# led.net
KiCad netlist of a schematic drawn in Altium Designer
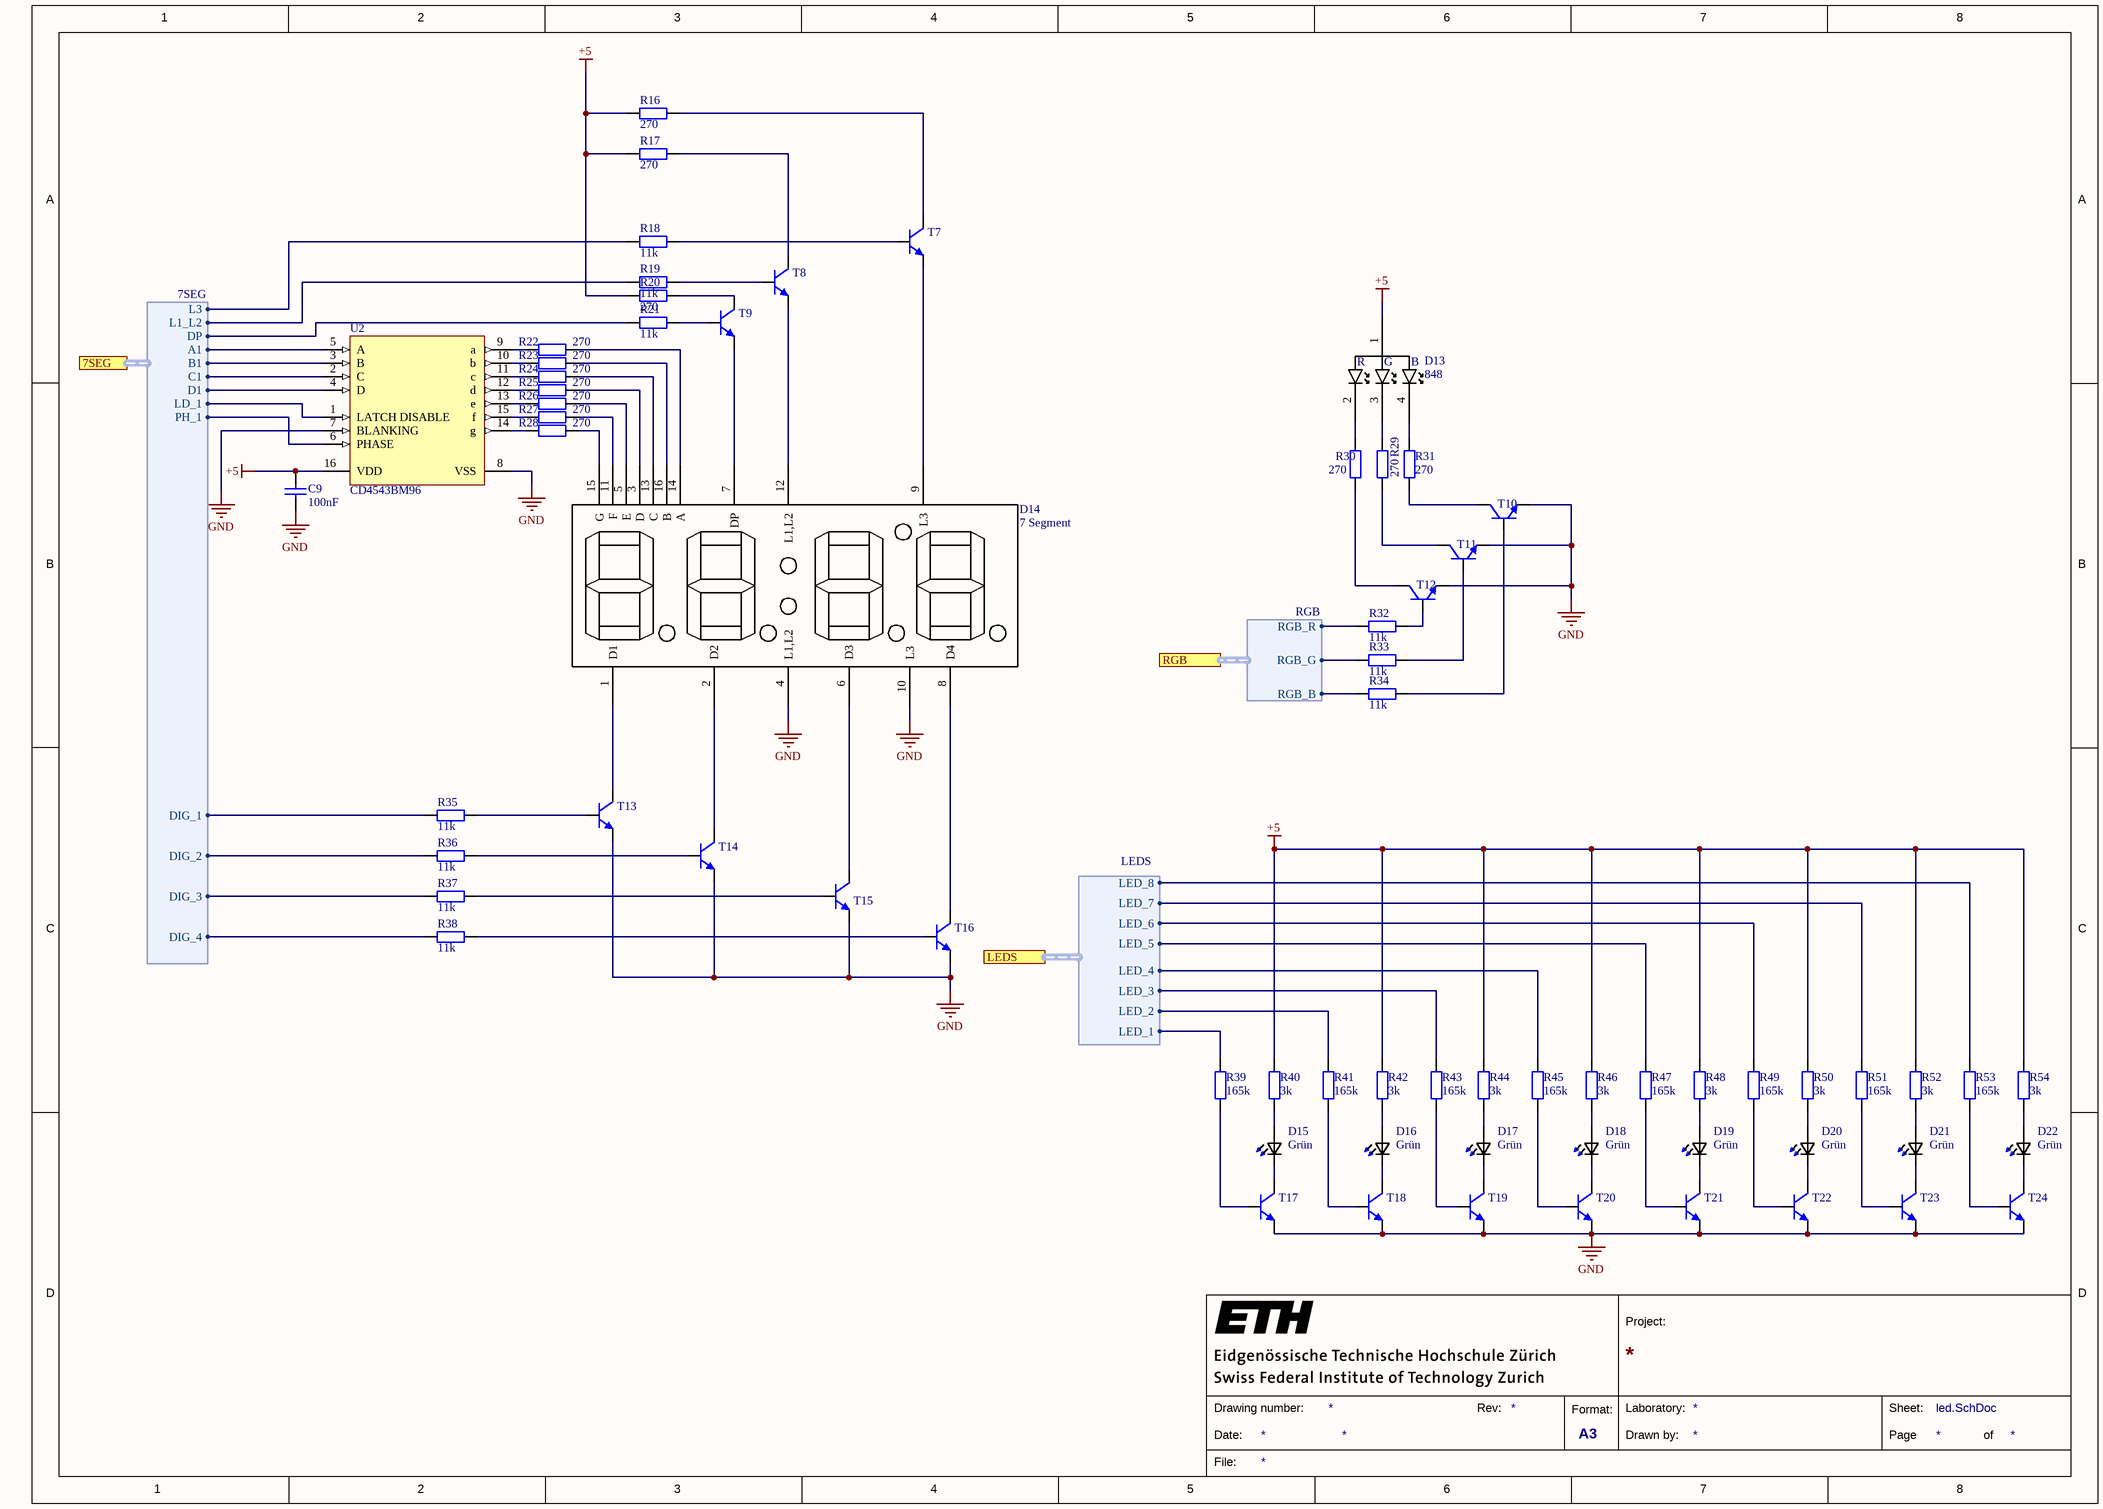
[diagram p0: led.SchDoc]

(export (version "E")
  (design (tool "Eeschema 10.0.6"))
  (components
    (comp (ref "C9")
      (value "100nF")
      (footprint "CAP_0603i_1608m -N")
      (description "capacitor")
      (libsource (lib "IDSC std generic parts") (part "Cap"))
    )
    (comp (ref "D13") (value "848") (footprint "Adafruit-848") (libsource (lib "LIB") (part "Adafruit-848")))
    (comp (ref "D14") (value "7 Segment") (footprint "TDCG1060M") (libsource (lib "LIB") (part "TDCG1060M")))
    (comp (ref "D15")
      (value "Grün")
      (footprint "*0603")
      (description "LED; SMD; 0603; gr黱; 35mcd; 1.6x0.8x0.55mm; 130掳; 2梅2.V; 20mA")
      (fields (field (name "MP") "LTST-C191KGKT") (field (name "DIGI-KEY_PART_NUMBER") "160-1446-1-ND"))
      (libsource (lib "Funk") (part "LTST-C191KGKT"))
    )
    (comp (ref "D16")
      (value "Grün")
      (footprint "*0603")
      (description "LED; SMD; 0603; gr黱; 35mcd; 1.6x0.8x0.55mm; 130掳; 2梅2.V; 20mA")
      (fields (field (name "MP") "LTST-C191KGKT") (field (name "DIGI-KEY_PART_NUMBER") "160-1446-1-ND"))
      (libsource (lib "Funk") (part "LTST-C191KGKT"))
    )
    (comp (ref "D17")
      (value "Grün")
      (footprint "*0603")
      (description "LED; SMD; 0603; gr黱; 35mcd; 1.6x0.8x0.55mm; 130掳; 2梅2.V; 20mA")
      (fields (field (name "MP") "LTST-C191KGKT") (field (name "DIGI-KEY_PART_NUMBER") "160-1446-1-ND"))
      (libsource (lib "Funk") (part "LTST-C191KGKT"))
    )
    (comp (ref "D18")
      (value "Grün")
      (footprint "*0603")
      (description "LED; SMD; 0603; gr黱; 35mcd; 1.6x0.8x0.55mm; 130掳; 2梅2.V; 20mA")
      (fields (field (name "MP") "LTST-C191KGKT") (field (name "DIGI-KEY_PART_NUMBER") "160-1446-1-ND"))
      (libsource (lib "Funk") (part "LTST-C191KGKT"))
    )
    (comp (ref "D19")
      (value "Grün")
      (footprint "*0603")
      (description "LED; SMD; 0603; gr黱; 35mcd; 1.6x0.8x0.55mm; 130掳; 2梅2.V; 20mA")
      (fields (field (name "MP") "LTST-C191KGKT") (field (name "DIGI-KEY_PART_NUMBER") "160-1446-1-ND"))
      (libsource (lib "Funk") (part "LTST-C191KGKT"))
    )
    (comp (ref "D20")
      (value "Grün")
      (footprint "*0603")
      (description "LED; SMD; 0603; gr黱; 35mcd; 1.6x0.8x0.55mm; 130掳; 2梅2.V; 20mA")
      (fields (field (name "MP") "LTST-C191KGKT") (field (name "DIGI-KEY_PART_NUMBER") "160-1446-1-ND"))
      (libsource (lib "Funk") (part "LTST-C191KGKT"))
    )
    (comp (ref "D21")
      (value "Grün")
      (footprint "*0603")
      (description "LED; SMD; 0603; gr黱; 35mcd; 1.6x0.8x0.55mm; 130掳; 2梅2.V; 20mA")
      (fields (field (name "MP") "LTST-C191KGKT") (field (name "DIGI-KEY_PART_NUMBER") "160-1446-1-ND"))
      (libsource (lib "Funk") (part "LTST-C191KGKT"))
    )
    (comp (ref "D22")
      (value "Grün")
      (footprint "*0603")
      (description "LED; SMD; 0603; gr黱; 35mcd; 1.6x0.8x0.55mm; 130掳; 2梅2.V; 20mA")
      (fields (field (name "MP") "LTST-C191KGKT") (field (name "DIGI-KEY_PART_NUMBER") "160-1446-1-ND"))
      (libsource (lib "Funk") (part "LTST-C191KGKT"))
    )
    (comp (ref "R16")
      (value "270")
      (footprint "RES_0603i_1608m -N")
      (description "Resistor")
      (libsource (lib "IDSC std generic parts") (part "Res"))
    )
    (comp (ref "R17")
      (value "270")
      (footprint "RES_0603i_1608m -N")
      (description "Resistor")
      (libsource (lib "IDSC std generic parts") (part "Res"))
    )
    (comp (ref "R18")
      (value "11k")
      (footprint "RES_0603i_1608m -N")
      (description "Resistor")
      (libsource (lib "IDSC std generic parts") (part "Res"))
    )
    (comp (ref "R19")
      (value "11k")
      (footprint "RES_0603i_1608m -N")
      (description "Resistor")
      (libsource (lib "IDSC std generic parts") (part "Res"))
    )
    (comp (ref "R20")
      (value "270")
      (footprint "RES_0603i_1608m -N")
      (description "Resistor")
      (libsource (lib "") (part "Res_2"))
    )
    (comp (ref "R21")
      (value "11k")
      (footprint "RES_0603i_1608m -N")
      (description "Resistor")
      (libsource (lib "") (part "Res_2"))
    )
    (comp (ref "R22")
      (value "270")
      (footprint "RES_0603i_1608m -N")
      (description "Resistor")
      (libsource (lib "IDSC std generic parts") (part "Res"))
    )
    (comp (ref "R23")
      (value "270")
      (footprint "RES_0603i_1608m -N")
      (description "Resistor")
      (libsource (lib "IDSC std generic parts") (part "Res"))
    )
    (comp (ref "R24")
      (value "270")
      (footprint "RES_0603i_1608m -N")
      (description "Resistor")
      (libsource (lib "IDSC std generic parts") (part "Res"))
    )
    (comp (ref "R25")
      (value "270")
      (footprint "RES_0603i_1608m -N")
      (description "Resistor")
      (libsource (lib "IDSC std generic parts") (part "Res"))
    )
    (comp (ref "R26")
      (value "270")
      (footprint "RES_0603i_1608m -N")
      (description "Resistor")
      (libsource (lib "IDSC std generic parts") (part "Res"))
    )
    (comp (ref "R27")
      (value "270")
      (footprint "RES_0603i_1608m -N")
      (description "Resistor")
      (libsource (lib "IDSC std generic parts") (part "Res"))
    )
    (comp (ref "R28")
      (value "270")
      (footprint "RES_0603i_1608m -N")
      (description "Resistor")
      (libsource (lib "IDSC std generic parts") (part "Res"))
    )
    (comp (ref "R29")
      (value "270")
      (footprint "RES_0603i_1608m -N")
      (description "Resistor")
      (libsource (lib "") (part "Res_1"))
    )
    (comp (ref "R30")
      (value "270")
      (footprint "RES_0603i_1608m -N")
      (description "Resistor")
      (libsource (lib "") (part "Res_1"))
    )
    (comp (ref "R31")
      (value "270")
      (footprint "RES_0603i_1608m -N")
      (description "Resistor")
      (libsource (lib "") (part "Res_1"))
    )
    (comp (ref "R32")
      (value "11k")
      (footprint "RES_0603i_1608m -N")
      (description "Resistor")
      (libsource (lib "") (part "Res_2"))
    )
    (comp (ref "R33")
      (value "11k")
      (footprint "RES_0603i_1608m -N")
      (description "Resistor")
      (libsource (lib "") (part "Res_2"))
    )
    (comp (ref "R34")
      (value "11k")
      (footprint "RES_0603i_1608m -N")
      (description "Resistor")
      (libsource (lib "") (part "Res_2"))
    )
    (comp (ref "R35")
      (value "11k")
      (footprint "RES_0603i_1608m -N")
      (description "Resistor")
      (libsource (lib "") (part "Res_2"))
    )
    (comp (ref "R36")
      (value "11k")
      (footprint "RES_0603i_1608m -N")
      (description "Resistor")
      (libsource (lib "") (part "Res_2"))
    )
    (comp (ref "R37")
      (value "11k")
      (footprint "RES_0603i_1608m -N")
      (description "Resistor")
      (libsource (lib "") (part "Res_2"))
    )
    (comp (ref "R38")
      (value "11k")
      (footprint "RES_0603i_1608m -N")
      (description "Resistor")
      (libsource (lib "") (part "Res_2"))
    )
    (comp (ref "R39")
      (value "165k")
      (footprint "RES_0603i_1608m -N")
      (description "Resistor")
      (libsource (lib "") (part "Res_1"))
    )
    (comp (ref "R40")
      (value "3k")
      (footprint "RES_0603i_1608m -N")
      (description "Resistor")
      (libsource (lib "") (part "Res_1"))
    )
    (comp (ref "R41")
      (value "165k")
      (footprint "RES_0603i_1608m -N")
      (description "Resistor")
      (libsource (lib "") (part "Res_1"))
    )
    (comp (ref "R42")
      (value "3k")
      (footprint "RES_0603i_1608m -N")
      (description "Resistor")
      (libsource (lib "") (part "Res_1"))
    )
    (comp (ref "R43")
      (value "165k")
      (footprint "RES_0603i_1608m -N")
      (description "Resistor")
      (libsource (lib "") (part "Res_1"))
    )
    (comp (ref "R44")
      (value "3k")
      (footprint "RES_0603i_1608m -N")
      (description "Resistor")
      (libsource (lib "") (part "Res_1"))
    )
    (comp (ref "R45")
      (value "165k")
      (footprint "RES_0603i_1608m -N")
      (description "Resistor")
      (libsource (lib "") (part "Res_1"))
    )
    (comp (ref "R46")
      (value "3k")
      (footprint "RES_0603i_1608m -N")
      (description "Resistor")
      (libsource (lib "") (part "Res_1"))
    )
    (comp (ref "R47")
      (value "165k")
      (footprint "RES_0603i_1608m -N")
      (description "Resistor")
      (libsource (lib "") (part "Res_1"))
    )
    (comp (ref "R48")
      (value "3k")
      (footprint "RES_0603i_1608m -N")
      (description "Resistor")
      (libsource (lib "") (part "Res_1"))
    )
    (comp (ref "R49")
      (value "165k")
      (footprint "RES_0603i_1608m -N")
      (description "Resistor")
      (libsource (lib "") (part "Res_1"))
    )
    (comp (ref "R50")
      (value "3k")
      (footprint "RES_0603i_1608m -N")
      (description "Resistor")
      (libsource (lib "") (part "Res_1"))
    )
    (comp (ref "R51")
      (value "165k")
      (footprint "RES_0603i_1608m -N")
      (description "Resistor")
      (libsource (lib "") (part "Res_1"))
    )
    (comp (ref "R52")
      (value "3k")
      (footprint "RES_0603i_1608m -N")
      (description "Resistor")
      (libsource (lib "") (part "Res_1"))
    )
    (comp (ref "R53")
      (value "165k")
      (footprint "RES_0603i_1608m -N")
      (description "Resistor")
      (libsource (lib "") (part "Res_1"))
    )
    (comp (ref "R54")
      (value "3k")
      (footprint "RES_0603i_1608m -N")
      (description "Resistor")
      (libsource (lib "") (part "Res_1"))
    )
    (comp (ref "T7")
      (value "Part Number: MMBT3904-7-F")
      (footprint "SOT-23-M")
      (description "No Description Available")
      (fields
        (field (name "MANUFACTURER_PART_NUMBER") "MMBT3904-7-F")
        (field (name "COPYRIGHT") "Copyright (C) 2018 Accelerated Designs. All rights reserved")
      )
      (libsource (lib "Funk") (part "MMBT3904-7-F"))
    )
    (comp (ref "T8")
      (value "Part Number: MMBT3904-7-F")
      (footprint "SOT-23-M")
      (description "No Description Available")
      (fields
        (field (name "MANUFACTURER_PART_NUMBER") "MMBT3904-7-F")
        (field (name "COPYRIGHT") "Copyright (C) 2018 Accelerated Designs. All rights reserved")
      )
      (libsource (lib "Funk") (part "MMBT3904-7-F"))
    )
    (comp (ref "T9")
      (value "Part Number: MMBT3904-7-F")
      (footprint "SOT-23-M")
      (description "No Description Available")
      (fields
        (field (name "MANUFACTURER_PART_NUMBER") "MMBT3904-7-F")
        (field (name "COPYRIGHT") "Copyright (C) 2018 Accelerated Designs. All rights reserved")
      )
      (libsource (lib "Funk") (part "MMBT3904-7-F"))
    )
    (comp (ref "T10")
      (value "Part Number: MMBT3904-7-F")
      (footprint "SOT-23-M")
      (description "No Description Available")
      (fields
        (field (name "MANUFACTURER_PART_NUMBER") "MMBT3904-7-F")
        (field (name "COPYRIGHT") "Copyright (C) 2018 Accelerated Designs. All rights reserved")
      )
      (libsource (lib "Funk") (part "MMBT3904-7-F"))
    )
    (comp (ref "T11")
      (value "Part Number: MMBT3904-7-F")
      (footprint "SOT-23-M")
      (description "No Description Available")
      (fields
        (field (name "MANUFACTURER_PART_NUMBER") "MMBT3904-7-F")
        (field (name "COPYRIGHT") "Copyright (C) 2018 Accelerated Designs. All rights reserved")
      )
      (libsource (lib "Funk") (part "MMBT3904-7-F"))
    )
    (comp (ref "T12")
      (value "Part Number: MMBT3904-7-F")
      (footprint "SOT-23-M")
      (description "No Description Available")
      (fields
        (field (name "MANUFACTURER_PART_NUMBER") "MMBT3904-7-F")
        (field (name "COPYRIGHT") "Copyright (C) 2018 Accelerated Designs. All rights reserved")
      )
      (libsource (lib "Funk") (part "MMBT3904-7-F"))
    )
    (comp (ref "T13")
      (value "Part Number: MMBT3904-7-F")
      (footprint "SOT-23-M")
      (description "No Description Available")
      (fields
        (field (name "MANUFACTURER_PART_NUMBER") "MMBT3904-7-F")
        (field (name "COPYRIGHT") "Copyright (C) 2018 Accelerated Designs. All rights reserved")
      )
      (libsource (lib "Funk") (part "MMBT3904-7-F"))
    )
    (comp (ref "T14")
      (value "Part Number: MMBT3904-7-F")
      (footprint "SOT-23-M")
      (description "No Description Available")
      (fields
        (field (name "MANUFACTURER_PART_NUMBER") "MMBT3904-7-F")
        (field (name "COPYRIGHT") "Copyright (C) 2018 Accelerated Designs. All rights reserved")
      )
      (libsource (lib "Funk") (part "MMBT3904-7-F"))
    )
    (comp (ref "T15")
      (value "Part Number: MMBT3904-7-F")
      (footprint "SOT-23-M")
      (description "No Description Available")
      (fields
        (field (name "MANUFACTURER_PART_NUMBER") "MMBT3904-7-F")
        (field (name "COPYRIGHT") "Copyright (C) 2018 Accelerated Designs. All rights reserved")
      )
      (libsource (lib "Funk") (part "MMBT3904-7-F"))
    )
    (comp (ref "T16")
      (value "Part Number: MMBT3904-7-F")
      (footprint "SOT-23-M")
      (description "No Description Available")
      (fields
        (field (name "MANUFACTURER_PART_NUMBER") "MMBT3904-7-F")
        (field (name "COPYRIGHT") "Copyright (C) 2018 Accelerated Designs. All rights reserved")
      )
      (libsource (lib "Funk") (part "MMBT3904-7-F"))
    )
    (comp (ref "T17")
      (value "Part Number: MMBT3904-7-F")
      (footprint "SOT-23-M")
      (description "No Description Available")
      (fields
        (field (name "MANUFACTURER_PART_NUMBER") "MMBT3904-7-F")
        (field (name "COPYRIGHT") "Copyright (C) 2018 Accelerated Designs. All rights reserved")
      )
      (libsource (lib "Funk") (part "MMBT3904-7-F"))
    )
    (comp (ref "T18")
      (value "Part Number: MMBT3904-7-F")
      (footprint "SOT-23-M")
      (description "No Description Available")
      (fields
        (field (name "MANUFACTURER_PART_NUMBER") "MMBT3904-7-F")
        (field (name "COPYRIGHT") "Copyright (C) 2018 Accelerated Designs. All rights reserved")
      )
      (libsource (lib "Funk") (part "MMBT3904-7-F"))
    )
    (comp (ref "T19")
      (value "Part Number: MMBT3904-7-F")
      (footprint "SOT-23-M")
      (description "No Description Available")
      (fields
        (field (name "MANUFACTURER_PART_NUMBER") "MMBT3904-7-F")
        (field (name "COPYRIGHT") "Copyright (C) 2018 Accelerated Designs. All rights reserved")
      )
      (libsource (lib "Funk") (part "MMBT3904-7-F"))
    )
    (comp (ref "T20")
      (value "Part Number: MMBT3904-7-F")
      (footprint "SOT-23-M")
      (description "No Description Available")
      (fields
        (field (name "MANUFACTURER_PART_NUMBER") "MMBT3904-7-F")
        (field (name "COPYRIGHT") "Copyright (C) 2018 Accelerated Designs. All rights reserved")
      )
      (libsource (lib "Funk") (part "MMBT3904-7-F"))
    )
    (comp (ref "T21")
      (value "Part Number: MMBT3904-7-F")
      (footprint "SOT-23-M")
      (description "No Description Available")
      (fields
        (field (name "MANUFACTURER_PART_NUMBER") "MMBT3904-7-F")
        (field (name "COPYRIGHT") "Copyright (C) 2018 Accelerated Designs. All rights reserved")
      )
      (libsource (lib "Funk") (part "MMBT3904-7-F"))
    )
    (comp (ref "T22")
      (value "Part Number: MMBT3904-7-F")
      (footprint "SOT-23-M")
      (description "No Description Available")
      (fields
        (field (name "MANUFACTURER_PART_NUMBER") "MMBT3904-7-F")
        (field (name "COPYRIGHT") "Copyright (C) 2018 Accelerated Designs. All rights reserved")
      )
      (libsource (lib "Funk") (part "MMBT3904-7-F"))
    )
    (comp (ref "T23")
      (value "Part Number: MMBT3904-7-F")
      (footprint "SOT-23-M")
      (description "No Description Available")
      (fields
        (field (name "MANUFACTURER_PART_NUMBER") "MMBT3904-7-F")
        (field (name "COPYRIGHT") "Copyright (C) 2018 Accelerated Designs. All rights reserved")
      )
      (libsource (lib "Funk") (part "MMBT3904-7-F"))
    )
    (comp (ref "T24")
      (value "Part Number: MMBT3904-7-F")
      (footprint "SOT-23-M")
      (description "No Description Available")
      (fields
        (field (name "MANUFACTURER_PART_NUMBER") "MMBT3904-7-F")
        (field (name "COPYRIGHT") "Copyright (C) 2018 Accelerated Designs. All rights reserved")
      )
      (libsource (lib "Funk") (part "MMBT3904-7-F"))
    )
    (comp (ref "U2")
      (value "CD4543BM96")
      (footprint "D0016A_L")
      (fields (field (name "MANUFACTURER") "Texas Instruments"))
      (libsource (lib "Altium Content Vault") (part "TI-CD4543B-16"))
    )
  )
  (nets
    (net (code "4") (name "+5") (class "Default")
      (node (ref "C9") (pin "2") (pinfunction "2_2") (pintype "passive"))
      (node (ref "D13") (pin "1") (pinfunction "25_1") (pintype "passive"))
      (node (ref "R16") (pin "2") (pinfunction "2_2") (pintype "passive"))
      (node (ref "R17") (pin "2") (pinfunction "2_2") (pintype "passive"))
      (node (ref "R20") (pin "1") (pinfunction "1_1") (pintype "passive"))
      (node (ref "R40") (pin "2") (pinfunction "2_2") (pintype "passive"))
      (node (ref "R42") (pin "2") (pinfunction "2_2") (pintype "passive"))
      (node (ref "R44") (pin "2") (pinfunction "2_2") (pintype "passive"))
      (node (ref "R46") (pin "2") (pinfunction "2_2") (pintype "passive"))
      (node (ref "R48") (pin "2") (pinfunction "2_2") (pintype "passive"))
      (node (ref "R50") (pin "2") (pinfunction "2_2") (pintype "passive"))
      (node (ref "R52") (pin "2") (pinfunction "2_2") (pintype "passive"))
      (node (ref "R54") (pin "2") (pinfunction "2_2") (pintype "passive"))
      (node (ref "U2") (pin "16") (pinfunction "VDD_16") (pintype "power_in"))
    )
    (net (code "5") (name "/A1") (class "Default")
      (node (ref "U2") (pin "5") (pinfunction "A_5") (pintype "input"))
    )
    (net (code "6") (name "/B1") (class "Default")
      (node (ref "U2") (pin "3") (pinfunction "B_3") (pintype "input"))
    )
    (net (code "7") (name "/C1") (class "Default")
      (node (ref "U2") (pin "2") (pinfunction "C_2") (pintype "input"))
    )
    (net (code "8") (name "/D1") (class "Default")
      (node (ref "U2") (pin "4") (pinfunction "D_4") (pintype "input"))
    )
    (net (code "9") (name "/DIG_1") (class "Default")
      (node (ref "R35") (pin "1") (pinfunction "1_1") (pintype "passive"))
    )
    (net (code "10") (name "/DIG_2") (class "Default")
      (node (ref "R36") (pin "1") (pinfunction "1_1") (pintype "passive"))
    )
    (net (code "11") (name "/DIG_3") (class "Default")
      (node (ref "R37") (pin "1") (pinfunction "1_1") (pintype "passive"))
    )
    (net (code "12") (name "/DIG_4") (class "Default")
      (node (ref "R38") (pin "1") (pinfunction "1_1") (pintype "passive"))
    )
    (net (code "13") (name "/DP") (class "Default")
      (node (ref "R21") (pin "1") (pinfunction "1_1") (pintype "passive"))
    )
    (net (code "14") (name "/L1_L2") (class "Default")
      (node (ref "R19") (pin "2") (pinfunction "2_2") (pintype "passive"))
    )
    (net (code "15") (name "/L3") (class "Default")
      (node (ref "R18") (pin "2") (pinfunction "2_2") (pintype "passive"))
    )
    (net (code "16") (name "/LD_1") (class "Default")
      (node (ref "U2") (pin "1") (pinfunction "LATCH_DISABLE_1") (pintype "input"))
    )
    (net (code "17") (name "/LED_1") (class "Default")
      (node (ref "R39") (pin "2") (pinfunction "2_2") (pintype "passive"))
    )
    (net (code "18") (name "/LED_2") (class "Default")
      (node (ref "R41") (pin "2") (pinfunction "2_2") (pintype "passive"))
    )
    (net (code "19") (name "/LED_3") (class "Default")
      (node (ref "R43") (pin "2") (pinfunction "2_2") (pintype "passive"))
    )
    (net (code "20") (name "/LED_4") (class "Default")
      (node (ref "R45") (pin "2") (pinfunction "2_2") (pintype "passive"))
    )
    (net (code "21") (name "/LED_5") (class "Default")
      (node (ref "R47") (pin "2") (pinfunction "2_2") (pintype "passive"))
    )
    (net (code "22") (name "/LED_6") (class "Default")
      (node (ref "R49") (pin "2") (pinfunction "2_2") (pintype "passive"))
    )
    (net (code "23") (name "/LED_7") (class "Default")
      (node (ref "R51") (pin "2") (pinfunction "2_2") (pintype "passive"))
    )
    (net (code "24") (name "/LED_8") (class "Default")
      (node (ref "R53") (pin "2") (pinfunction "2_2") (pintype "passive"))
    )
    (net (code "25") (name "/PH_1") (class "Default")
      (node (ref "U2") (pin "6") (pinfunction "PHASE_6") (pintype "input"))
    )
    (net (code "26") (name "/RGB_B") (class "Default")
      (node (ref "R34") (pin "1") (pinfunction "1_1") (pintype "passive"))
    )
    (net (code "27") (name "/RGB_G") (class "Default")
      (node (ref "R33") (pin "1") (pinfunction "1_1") (pintype "passive"))
    )
    (net (code "28") (name "/RGB_R") (class "Default")
      (node (ref "R32") (pin "1") (pinfunction "1_1") (pintype "passive"))
    )
    (net (code "32") (name "GND") (class "Default")
      (node (ref "C9") (pin "1") (pinfunction "1_1") (pintype "passive"))
      (node (ref "D14") (pin "10") (pinfunction "L3_10") (pintype "passive"))
      (node (ref "D14") (pin "4") (pinfunction "L1,L2_4") (pintype "passive"))
      (node (ref "T10") (pin "2") (pinfunction "E_2") (pintype "passive"))
      (node (ref "T11") (pin "2") (pinfunction "E_2") (pintype "passive"))
      (node (ref "T12") (pin "2") (pinfunction "E_2") (pintype "passive"))
      (node (ref "T13") (pin "2") (pinfunction "E_2") (pintype "passive"))
      (node (ref "T14") (pin "2") (pinfunction "E_2") (pintype "passive"))
      (node (ref "T15") (pin "2") (pinfunction "E_2") (pintype "passive"))
      (node (ref "T16") (pin "2") (pinfunction "E_2") (pintype "passive"))
      (node (ref "T17") (pin "2") (pinfunction "E_2") (pintype "passive"))
      (node (ref "T18") (pin "2") (pinfunction "E_2") (pintype "passive"))
      (node (ref "T19") (pin "2") (pinfunction "E_2") (pintype "passive"))
      (node (ref "T20") (pin "2") (pinfunction "E_2") (pintype "passive"))
      (node (ref "T21") (pin "2") (pinfunction "E_2") (pintype "passive"))
      (node (ref "T22") (pin "2") (pinfunction "E_2") (pintype "passive"))
      (node (ref "T23") (pin "2") (pinfunction "E_2") (pintype "passive"))
      (node (ref "T24") (pin "2") (pinfunction "E_2") (pintype "passive"))
      (node (ref "U2") (pin "7") (pinfunction "BLANKING_7") (pintype "input"))
      (node (ref "U2") (pin "8") (pinfunction "VSS_8") (pintype "power_in"))
    )
    (net (code "33") (name "Net-(D13-26)") (class "Default")
      (node (ref "D13") (pin "2") (pinfunction "26_2") (pintype "passive"))
      (node (ref "R30") (pin "2") (pinfunction "2_2") (pintype "passive"))
    )
    (net (code "34") (name "Net-(D13-27)") (class "Default")
      (node (ref "D13") (pin "3") (pinfunction "27_3") (pintype "passive"))
      (node (ref "R29") (pin "2") (pinfunction "2_2") (pintype "passive"))
    )
    (net (code "35") (name "Net-(D13-28)") (class "Default")
      (node (ref "D13") (pin "4") (pinfunction "28_4") (pintype "passive"))
      (node (ref "R31") (pin "2") (pinfunction "2_2") (pintype "passive"))
    )
    (net (code "36") (name "Net-(D14-A)") (class "Default")
      (node (ref "D14") (pin "14") (pinfunction "A_14") (pintype "passive"))
      (node (ref "R22") (pin "1") (pinfunction "1_1") (pintype "passive"))
    )
    (net (code "37") (name "Net-(D14-B)") (class "Default")
      (node (ref "D14") (pin "16") (pinfunction "B_16") (pintype "passive"))
      (node (ref "R23") (pin "1") (pinfunction "1_1") (pintype "passive"))
    )
    (net (code "38") (name "Net-(D14-C)") (class "Default")
      (node (ref "D14") (pin "13") (pinfunction "C_13") (pintype "passive"))
      (node (ref "R24") (pin "1") (pinfunction "1_1") (pintype "passive"))
    )
    (net (code "39") (name "Net-(D14-D)") (class "Default")
      (node (ref "D14") (pin "3") (pinfunction "D_3") (pintype "passive"))
      (node (ref "R25") (pin "1") (pinfunction "1_1") (pintype "passive"))
    )
    (net (code "40") (name "Net-(D14-D1)") (class "Default")
      (node (ref "D14") (pin "1") (pinfunction "D1_1") (pintype "passive"))
      (node (ref "T13") (pin "3") (pinfunction "C_3") (pintype "passive"))
    )
    (net (code "41") (name "Net-(D14-D2)") (class "Default")
      (node (ref "D14") (pin "2") (pinfunction "D2_2") (pintype "passive"))
      (node (ref "T14") (pin "3") (pinfunction "C_3") (pintype "passive"))
    )
    (net (code "42") (name "Net-(D14-D3)") (class "Default")
      (node (ref "D14") (pin "6") (pinfunction "D3_6") (pintype "passive"))
      (node (ref "T15") (pin "3") (pinfunction "C_3") (pintype "passive"))
    )
    (net (code "43") (name "Net-(D14-D4)") (class "Default")
      (node (ref "D14") (pin "8") (pinfunction "D4_8") (pintype "passive"))
      (node (ref "T16") (pin "3") (pinfunction "C_3") (pintype "passive"))
    )
    (net (code "44") (name "Net-(D14-DP)") (class "Default")
      (node (ref "D14") (pin "7") (pinfunction "DP_7") (pintype "passive"))
      (node (ref "T9") (pin "2") (pinfunction "E_2") (pintype "passive"))
    )
    (net (code "45") (name "Net-(D14-E)") (class "Default")
      (node (ref "D14") (pin "5") (pinfunction "E_5") (pintype "passive"))
      (node (ref "R26") (pin "1") (pinfunction "1_1") (pintype "passive"))
    )
    (net (code "46") (name "Net-(D14-F)") (class "Default")
      (node (ref "D14") (pin "11") (pinfunction "F_11") (pintype "passive"))
      (node (ref "R27") (pin "1") (pinfunction "1_1") (pintype "passive"))
    )
    (net (code "47") (name "Net-(D14-G)") (class "Default")
      (node (ref "D14") (pin "15") (pinfunction "G_15") (pintype "passive"))
      (node (ref "R28") (pin "1") (pinfunction "1_1") (pintype "passive"))
    )
    (net (code "48") (name "Net-(D15-A2)") (class "Default")
      (node (ref "D15") (pin "2") (pinfunction "A2_2") (pintype "passive"))
      (node (ref "R40") (pin "1") (pinfunction "1_1") (pintype "passive"))
    )
    (net (code "49") (name "Net-(D15-K2)") (class "Default")
      (node (ref "D15") (pin "1") (pinfunction "K2_1") (pintype "passive"))
      (node (ref "T17") (pin "3") (pinfunction "C_3") (pintype "passive"))
    )
    (net (code "50") (name "Net-(D16-A2)") (class "Default")
      (node (ref "D16") (pin "2") (pinfunction "A2_2") (pintype "passive"))
      (node (ref "R42") (pin "1") (pinfunction "1_1") (pintype "passive"))
    )
    (net (code "51") (name "Net-(D16-K2)") (class "Default")
      (node (ref "D16") (pin "1") (pinfunction "K2_1") (pintype "passive"))
      (node (ref "T18") (pin "3") (pinfunction "C_3") (pintype "passive"))
    )
    (net (code "52") (name "Net-(D17-A2)") (class "Default")
      (node (ref "D17") (pin "2") (pinfunction "A2_2") (pintype "passive"))
      (node (ref "R44") (pin "1") (pinfunction "1_1") (pintype "passive"))
    )
    (net (code "53") (name "Net-(D17-K2)") (class "Default")
      (node (ref "D17") (pin "1") (pinfunction "K2_1") (pintype "passive"))
      (node (ref "T19") (pin "3") (pinfunction "C_3") (pintype "passive"))
    )
    (net (code "54") (name "Net-(D18-A2)") (class "Default")
      (node (ref "D18") (pin "2") (pinfunction "A2_2") (pintype "passive"))
      (node (ref "R46") (pin "1") (pinfunction "1_1") (pintype "passive"))
    )
    (net (code "55") (name "Net-(D18-K2)") (class "Default")
      (node (ref "D18") (pin "1") (pinfunction "K2_1") (pintype "passive"))
      (node (ref "T20") (pin "3") (pinfunction "C_3") (pintype "passive"))
    )
    (net (code "56") (name "Net-(D19-A2)") (class "Default")
      (node (ref "D19") (pin "2") (pinfunction "A2_2") (pintype "passive"))
      (node (ref "R48") (pin "1") (pinfunction "1_1") (pintype "passive"))
    )
    (net (code "57") (name "Net-(D19-K2)") (class "Default")
      (node (ref "D19") (pin "1") (pinfunction "K2_1") (pintype "passive"))
      (node (ref "T21") (pin "3") (pinfunction "C_3") (pintype "passive"))
    )
    (net (code "58") (name "Net-(D20-A2)") (class "Default")
      (node (ref "D20") (pin "2") (pinfunction "A2_2") (pintype "passive"))
      (node (ref "R50") (pin "1") (pinfunction "1_1") (pintype "passive"))
    )
    (net (code "59") (name "Net-(D20-K2)") (class "Default")
      (node (ref "D20") (pin "1") (pinfunction "K2_1") (pintype "passive"))
      (node (ref "T22") (pin "3") (pinfunction "C_3") (pintype "passive"))
    )
    (net (code "60") (name "Net-(D21-A2)") (class "Default")
      (node (ref "D21") (pin "2") (pinfunction "A2_2") (pintype "passive"))
      (node (ref "R52") (pin "1") (pinfunction "1_1") (pintype "passive"))
    )
    (net (code "61") (name "Net-(D21-K2)") (class "Default")
      (node (ref "D21") (pin "1") (pinfunction "K2_1") (pintype "passive"))
      (node (ref "T23") (pin "3") (pinfunction "C_3") (pintype "passive"))
    )
    (net (code "62") (name "Net-(D22-A2)") (class "Default")
      (node (ref "D22") (pin "2") (pinfunction "A2_2") (pintype "passive"))
      (node (ref "R54") (pin "1") (pinfunction "1_1") (pintype "passive"))
    )
    (net (code "63") (name "Net-(D22-K2)") (class "Default")
      (node (ref "D22") (pin "1") (pinfunction "K2_1") (pintype "passive"))
      (node (ref "T24") (pin "3") (pinfunction "C_3") (pintype "passive"))
    )
    (net (code "64") (name "Net-(T7-B)") (class "Default")
      (node (ref "R18") (pin "1") (pinfunction "1_1") (pintype "passive"))
      (node (ref "T7") (pin "1") (pinfunction "B_1") (pintype "passive"))
    )
    (net (code "65") (name "Net-(T7-C)") (class "Default")
      (node (ref "R16") (pin "1") (pinfunction "1_1") (pintype "passive"))
      (node (ref "T7") (pin "3") (pinfunction "C_3") (pintype "passive"))
    )
    (net (code "66") (name "Net-(T7-E)") (class "Default")
      (node (ref "D14") (pin "9") (pinfunction "L3_9") (pintype "passive"))
      (node (ref "T7") (pin "2") (pinfunction "E_2") (pintype "passive"))
    )
    (net (code "67") (name "Net-(T8-B)") (class "Default")
      (node (ref "R19") (pin "1") (pinfunction "1_1") (pintype "passive"))
      (node (ref "T8") (pin "1") (pinfunction "B_1") (pintype "passive"))
    )
    (net (code "68") (name "Net-(T8-C)") (class "Default")
      (node (ref "R17") (pin "1") (pinfunction "1_1") (pintype "passive"))
      (node (ref "T8") (pin "3") (pinfunction "C_3") (pintype "passive"))
    )
    (net (code "69") (name "Net-(T8-E)") (class "Default")
      (node (ref "D14") (pin "12") (pinfunction "L1,L2_12") (pintype "passive"))
      (node (ref "T8") (pin "2") (pinfunction "E_2") (pintype "passive"))
    )
    (net (code "70") (name "Net-(T9-B)") (class "Default")
      (node (ref "R21") (pin "2") (pinfunction "2_2") (pintype "passive"))
      (node (ref "T9") (pin "1") (pinfunction "B_1") (pintype "passive"))
    )
    (net (code "71") (name "Net-(T9-C)") (class "Default")
      (node (ref "R20") (pin "2") (pinfunction "2_2") (pintype "passive"))
      (node (ref "T9") (pin "3") (pinfunction "C_3") (pintype "passive"))
    )
    (net (code "72") (name "Net-(T10-B)") (class "Default")
      (node (ref "R34") (pin "2") (pinfunction "2_2") (pintype "passive"))
      (node (ref "T10") (pin "1") (pinfunction "B_1") (pintype "passive"))
    )
    (net (code "73") (name "Net-(T10-C)") (class "Default")
      (node (ref "R31") (pin "1") (pinfunction "1_1") (pintype "passive"))
      (node (ref "T10") (pin "3") (pinfunction "C_3") (pintype "passive"))
    )
    (net (code "74") (name "Net-(T11-B)") (class "Default")
      (node (ref "R33") (pin "2") (pinfunction "2_2") (pintype "passive"))
      (node (ref "T11") (pin "1") (pinfunction "B_1") (pintype "passive"))
    )
    (net (code "75") (name "Net-(T11-C)") (class "Default")
      (node (ref "R29") (pin "1") (pinfunction "1_1") (pintype "passive"))
      (node (ref "T11") (pin "3") (pinfunction "C_3") (pintype "passive"))
    )
    (net (code "76") (name "Net-(T12-B)") (class "Default")
      (node (ref "R32") (pin "2") (pinfunction "2_2") (pintype "passive"))
      (node (ref "T12") (pin "1") (pinfunction "B_1") (pintype "passive"))
    )
    (net (code "77") (name "Net-(T12-C)") (class "Default")
      (node (ref "R30") (pin "1") (pinfunction "1_1") (pintype "passive"))
      (node (ref "T12") (pin "3") (pinfunction "C_3") (pintype "passive"))
    )
    (net (code "78") (name "Net-(T13-B)") (class "Default")
      (node (ref "R35") (pin "2") (pinfunction "2_2") (pintype "passive"))
      (node (ref "T13") (pin "1") (pinfunction "B_1") (pintype "passive"))
    )
    (net (code "79") (name "Net-(T14-B)") (class "Default")
      (node (ref "R36") (pin "2") (pinfunction "2_2") (pintype "passive"))
      (node (ref "T14") (pin "1") (pinfunction "B_1") (pintype "passive"))
    )
    (net (code "80") (name "Net-(T15-B)") (class "Default")
      (node (ref "R37") (pin "2") (pinfunction "2_2") (pintype "passive"))
      (node (ref "T15") (pin "1") (pinfunction "B_1") (pintype "passive"))
    )
    (net (code "81") (name "Net-(T16-B)") (class "Default")
      (node (ref "R38") (pin "2") (pinfunction "2_2") (pintype "passive"))
      (node (ref "T16") (pin "1") (pinfunction "B_1") (pintype "passive"))
    )
    (net (code "82") (name "Net-(T17-B)") (class "Default")
      (node (ref "R39") (pin "1") (pinfunction "1_1") (pintype "passive"))
      (node (ref "T17") (pin "1") (pinfunction "B_1") (pintype "passive"))
    )
    (net (code "83") (name "Net-(T18-B)") (class "Default")
      (node (ref "R41") (pin "1") (pinfunction "1_1") (pintype "passive"))
      (node (ref "T18") (pin "1") (pinfunction "B_1") (pintype "passive"))
    )
    (net (code "84") (name "Net-(T19-B)") (class "Default")
      (node (ref "R43") (pin "1") (pinfunction "1_1") (pintype "passive"))
      (node (ref "T19") (pin "1") (pinfunction "B_1") (pintype "passive"))
    )
    (net (code "85") (name "Net-(T20-B)") (class "Default")
      (node (ref "R45") (pin "1") (pinfunction "1_1") (pintype "passive"))
      (node (ref "T20") (pin "1") (pinfunction "B_1") (pintype "passive"))
    )
    (net (code "86") (name "Net-(T21-B)") (class "Default")
      (node (ref "R47") (pin "1") (pinfunction "1_1") (pintype "passive"))
      (node (ref "T21") (pin "1") (pinfunction "B_1") (pintype "passive"))
    )
    (net (code "87") (name "Net-(T22-B)") (class "Default")
      (node (ref "R49") (pin "1") (pinfunction "1_1") (pintype "passive"))
      (node (ref "T22") (pin "1") (pinfunction "B_1") (pintype "passive"))
    )
    (net (code "88") (name "Net-(T23-B)") (class "Default")
      (node (ref "R51") (pin "1") (pinfunction "1_1") (pintype "passive"))
      (node (ref "T23") (pin "1") (pinfunction "B_1") (pintype "passive"))
    )
    (net (code "89") (name "Net-(T24-B)") (class "Default")
      (node (ref "R53") (pin "1") (pinfunction "1_1") (pintype "passive"))
      (node (ref "T24") (pin "1") (pinfunction "B_1") (pintype "passive"))
    )
    (net (code "90") (name "Net-(U2-a)") (class "Default")
      (node (ref "R22") (pin "2") (pinfunction "2_2") (pintype "passive"))
      (node (ref "U2") (pin "9") (pinfunction "a_9") (pintype "output"))
    )
    (net (code "91") (name "Net-(U2-b)") (class "Default")
      (node (ref "R23") (pin "2") (pinfunction "2_2") (pintype "passive"))
      (node (ref "U2") (pin "10") (pinfunction "b_10") (pintype "output"))
    )
    (net (code "92") (name "Net-(U2-c)") (class "Default")
      (node (ref "R24") (pin "2") (pinfunction "2_2") (pintype "passive"))
      (node (ref "U2") (pin "11") (pinfunction "c_11") (pintype "output"))
    )
    (net (code "93") (name "Net-(U2-d)") (class "Default")
      (node (ref "R25") (pin "2") (pinfunction "2_2") (pintype "passive"))
      (node (ref "U2") (pin "12") (pinfunction "d_12") (pintype "output"))
    )
    (net (code "94") (name "Net-(U2-e)") (class "Default")
      (node (ref "R26") (pin "2") (pinfunction "2_2") (pintype "passive"))
      (node (ref "U2") (pin "13") (pinfunction "e_13") (pintype "output"))
    )
    (net (code "95") (name "Net-(U2-f)") (class "Default")
      (node (ref "R27") (pin "2") (pinfunction "2_2") (pintype "passive"))
      (node (ref "U2") (pin "15") (pinfunction "f_15") (pintype "output"))
    )
    (net (code "96") (name "Net-(U2-g)") (class "Default")
      (node (ref "R28") (pin "2") (pinfunction "2_2") (pintype "passive"))
      (node (ref "U2") (pin "14") (pinfunction "g_14") (pintype "output"))
    )
  )
)
